# Adafruit_AirLift_Breakout.net
KiCad netlist of a schematic drawn in EAGLE
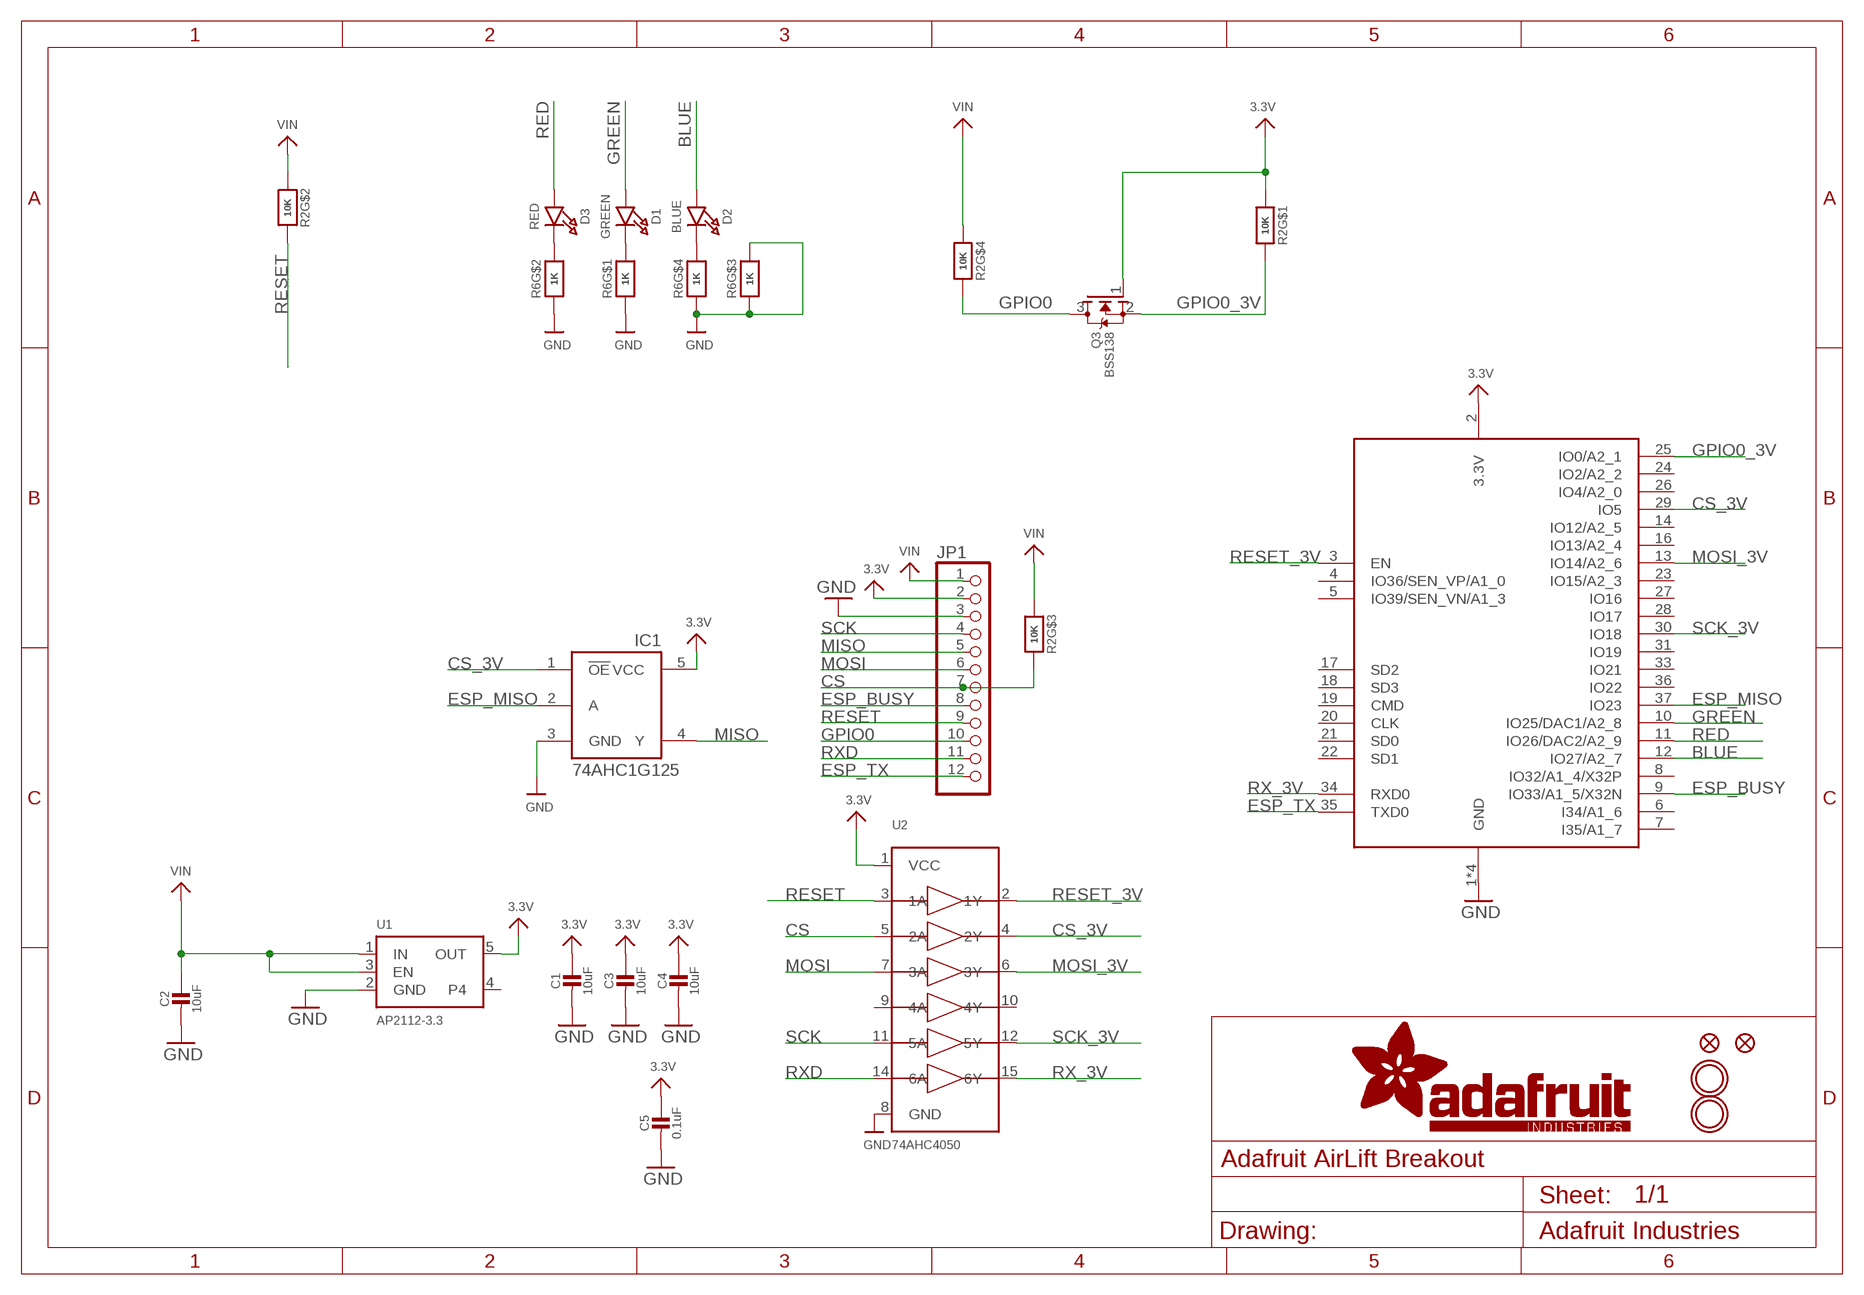
[diagram p0: schematic, sheet 1]

(export (version "E")
  (design (tool "Eeschema 10.0.6"))
  (components
    (comp (ref "C1")
      (value "10uF")
      (footprint "eagle-import:0805-NO")
      (libsource (lib "eagle-import") (part "CAP_CERAMIC0805-NOOUTLINE"))
    )
    (comp (ref "C2")
      (value "10uF")
      (footprint "eagle-import:0805-NO")
      (libsource (lib "eagle-import") (part "CAP_CERAMIC0805-NOOUTLINE"))
    )
    (comp (ref "C3")
      (value "10uF")
      (footprint "eagle-import:0805-NO")
      (libsource (lib "eagle-import") (part "CAP_CERAMIC0805-NOOUTLINE"))
    )
    (comp (ref "C4")
      (value "10uF")
      (footprint "eagle-import:0805-NO")
      (libsource (lib "eagle-import") (part "CAP_CERAMIC0805-NOOUTLINE"))
    )
    (comp (ref "C5")
      (value "0.1uF")
      (footprint "eagle-import:0603-NO")
      (libsource (lib "eagle-import") (part "CAP_CERAMIC0603_NO"))
    )
    (comp (ref "D1")
      (value "GREEN")
      (footprint "eagle-import:CHIPLED_0603_NOOUTLINE")
      (libsource (lib "eagle-import") (part "LED0603_NOOUTLINE"))
    )
    (comp (ref "D2")
      (value "BLUE")
      (footprint "eagle-import:CHIPLED_0603_NOOUTLINE")
      (libsource (lib "eagle-import") (part "LED0603_NOOUTLINE"))
    )
    (comp (ref "D3")
      (value "RED")
      (footprint "eagle-import:CHIPLED_0603_NOOUTLINE")
      (libsource (lib "eagle-import") (part "LED0603_NOOUTLINE"))
    )
    (comp (ref "FID1")
      (value "FIDUCIAL_1MM")
      (footprint "eagle-import:FIDUCIAL_1MM")
      (libsource (lib "eagle-import") (part "FIDUCIAL_1MM"))
    )
    (comp (ref "FID3")
      (value "FIDUCIAL_1MM")
      (footprint "eagle-import:FIDUCIAL_1MM")
      (libsource (lib "eagle-import") (part "FIDUCIAL_1MM"))
    )
    (comp (ref "IC1")
      (value "74AHC1G125")
      (footprint "eagle-import:SOT23-5L")
      (libsource (lib "eagle-import") (part "74AHC1G125"))
    )
    (comp (ref "JP1")
      (value "HEADER-1X12")
      (footprint "eagle-import:1X12_ROUND")
      (libsource (lib "eagle-import") (part "HEADER-1X12"))
    )
    (comp (ref "Q3")
      (value "BSS138")
      (footprint "eagle-import:SOT23-WIDE")
      (libsource (lib "eagle-import") (part "MOSFET-NWIDE"))
    )
    (comp (ref "R2")
      (value "10K")
      (footprint "eagle-import:RESPACK_4X0603")
      (libsource (lib "eagle-import") (part "RESISTOR_4PACK"))
    )
    (comp (ref "R6")
      (value "1K")
      (footprint "eagle-import:RESPACK_4X0603")
      (libsource (lib "eagle-import") (part "RESISTOR_4PACK"))
    )
    (comp (ref "U$15")
      (value "MOUNTINGHOLE2.5")
      (footprint "eagle-import:MOUNTINGHOLE_2.5_PLATED")
      (libsource (lib "eagle-import") (part "MOUNTINGHOLE2.5"))
    )
    (comp (ref "U$16")
      (value "MOUNTINGHOLE2.5")
      (footprint "eagle-import:MOUNTINGHOLE_2.5_PLATED")
      (libsource (lib "eagle-import") (part "MOUNTINGHOLE2.5"))
    )
    (comp (ref "U1")
      (value "AP2112-3.3")
      (footprint "eagle-import:SOT23-5")
      (libsource (lib "eagle-import") (part "VREG_SOT23-5"))
    )
    (comp (ref "U2")
      (value "74AHC4050")
      (footprint "eagle-import:TSSOP16")
      (libsource (lib "eagle-import") (part "74HC4050DTSSOP"))
    )
    (comp (ref "X1")
      (value "ESP32_WROOM32")
      (footprint "eagle-import:WROOM32")
      (libsource (lib "eagle-import") (part "ESP32_WROOM32"))
    )
  )
  (nets
    (net (code "1") (name "/BLUE") (class "Default")
      (node (ref "D2") (pin "A") (pinfunction "A_A") (pintype "passive"))
      (node (ref "X1") (pin "12") (pinfunction "IO27/A2_7_12") (pintype "bidirectional"))
    )
    (net (code "2") (name "/CS") (class "Default")
      (node (ref "JP1") (pin "7") (pinfunction "7_7") (pintype "passive"))
      (node (ref "R2") (pin "6") (pinfunction "2_6") (pintype "passive"))
      (node (ref "U2") (pin "5") (pinfunction "2A_5") (pintype "bidirectional"))
    )
    (net (code "3") (name "/CS_3V") (class "Default")
      (node (ref "IC1") (pin "1") (pinfunction "~{OE}_1") (pintype "input"))
      (node (ref "U2") (pin "4") (pinfunction "2Y_4") (pintype "bidirectional"))
      (node (ref "X1") (pin "29") (pinfunction "IO5_29") (pintype "bidirectional"))
    )
    (net (code "4") (name "/ESP_BUSY") (class "Default")
      (node (ref "JP1") (pin "8") (pinfunction "8_8") (pintype "passive"))
      (node (ref "X1") (pin "9") (pinfunction "IO33/A1_5/X32N_9") (pintype "bidirectional"))
    )
    (net (code "5") (name "/ESP_MISO") (class "Default")
      (node (ref "IC1") (pin "2") (pinfunction "A_2") (pintype "input"))
      (node (ref "X1") (pin "37") (pinfunction "IO23_37") (pintype "bidirectional"))
    )
    (net (code "6") (name "/ESP_TX") (class "Default")
      (node (ref "JP1") (pin "12") (pinfunction "12_12") (pintype "passive"))
      (node (ref "X1") (pin "35") (pinfunction "TXD0_35") (pintype "output"))
    )
    (net (code "7") (name "/GPIO0") (class "Default")
      (node (ref "JP1") (pin "10") (pinfunction "10_10") (pintype "passive"))
      (node (ref "Q3") (pin "3") (pinfunction "D_3") (pintype "bidirectional"))
      (node (ref "R2") (pin "4") (pinfunction "1_4") (pintype "passive"))
    )
    (net (code "8") (name "/GPIO0_3V") (class "Default")
      (node (ref "Q3") (pin "2") (pinfunction "S_2") (pintype "bidirectional"))
      (node (ref "R2") (pin "1") (pinfunction "1_1") (pintype "passive"))
      (node (ref "X1") (pin "25") (pinfunction "IO0/A2_1_25") (pintype "bidirectional"))
    )
    (net (code "9") (name "/GREEN") (class "Default")
      (node (ref "D1") (pin "A") (pinfunction "A_A") (pintype "passive"))
      (node (ref "X1") (pin "10") (pinfunction "IO25/DAC1/A2_8_10") (pintype "bidirectional"))
    )
    (net (code "10") (name "/MISO") (class "Default")
      (node (ref "IC1") (pin "4") (pinfunction "Y_4") (pintype "output"))
      (node (ref "JP1") (pin "5") (pinfunction "5_5") (pintype "passive"))
    )
    (net (code "11") (name "/MOSI") (class "Default")
      (node (ref "JP1") (pin "6") (pinfunction "6_6") (pintype "passive"))
      (node (ref "U2") (pin "7") (pinfunction "3A_7") (pintype "bidirectional"))
    )
    (net (code "12") (name "/MOSI_3V") (class "Default")
      (node (ref "U2") (pin "6") (pinfunction "3Y_6") (pintype "bidirectional"))
      (node (ref "X1") (pin "13") (pinfunction "IO14/A2_6_13") (pintype "bidirectional"))
    )
    (net (code "13") (name "/RED") (class "Default")
      (node (ref "D3") (pin "A") (pinfunction "A_A") (pintype "passive"))
      (node (ref "X1") (pin "11") (pinfunction "IO26/DAC2/A2_9_11") (pintype "bidirectional"))
    )
    (net (code "14") (name "/RESET") (class "Default")
      (node (ref "JP1") (pin "9") (pinfunction "9_9") (pintype "passive"))
      (node (ref "R2") (pin "7") (pinfunction "2_7") (pintype "passive"))
      (node (ref "U2") (pin "3") (pinfunction "1A_3") (pintype "bidirectional"))
    )
    (net (code "15") (name "/RESET_3V") (class "Default")
      (node (ref "U2") (pin "2") (pinfunction "1Y_2") (pintype "bidirectional"))
      (node (ref "X1") (pin "3") (pinfunction "EN_3") (pintype "input"))
    )
    (net (code "16") (name "/RXD") (class "Default")
      (node (ref "JP1") (pin "11") (pinfunction "11_11") (pintype "passive"))
      (node (ref "U2") (pin "14") (pinfunction "6A_14") (pintype "bidirectional"))
    )
    (net (code "17") (name "/RX_3V") (class "Default")
      (node (ref "U2") (pin "15") (pinfunction "6Y_15") (pintype "bidirectional"))
      (node (ref "X1") (pin "34") (pinfunction "RXD0_34") (pintype "input"))
    )
    (net (code "18") (name "/SCK") (class "Default")
      (node (ref "JP1") (pin "4") (pinfunction "4_4") (pintype "passive"))
      (node (ref "U2") (pin "11") (pinfunction "5A_11") (pintype "bidirectional"))
    )
    (net (code "19") (name "/SCK_3V") (class "Default")
      (node (ref "U2") (pin "12") (pinfunction "5Y_12") (pintype "bidirectional"))
      (node (ref "X1") (pin "30") (pinfunction "IO18_30") (pintype "bidirectional"))
    )
    (net (code "20") (name "3.3V") (class "Default")
      (node (ref "C1") (pin "1") (pinfunction "1_1") (pintype "passive"))
      (node (ref "C3") (pin "1") (pinfunction "1_1") (pintype "passive"))
      (node (ref "C4") (pin "1") (pinfunction "1_1") (pintype "passive"))
      (node (ref "C5") (pin "1") (pinfunction "1_1") (pintype "passive"))
      (node (ref "IC1") (pin "5") (pinfunction "VCC_5") (pintype "power_in"))
      (node (ref "JP1") (pin "2") (pinfunction "2_2") (pintype "passive"))
      (node (ref "Q3") (pin "1") (pinfunction "G_1") (pintype "bidirectional"))
      (node (ref "R2") (pin "8") (pinfunction "2_8") (pintype "passive"))
      (node (ref "U1") (pin "5") (pinfunction "OUT_5") (pintype "power_in"))
      (node (ref "U2") (pin "1") (pinfunction "VCC_1") (pintype "bidirectional"))
      (node (ref "X1") (pin "2") (pinfunction "3.3V_2") (pintype "passive"))
    )
    (net (code "21") (name "GND") (class "Default")
      (node (ref "C1") (pin "2") (pinfunction "2_2") (pintype "passive"))
      (node (ref "C2") (pin "2") (pinfunction "2_2") (pintype "passive"))
      (node (ref "C3") (pin "2") (pinfunction "2_2") (pintype "passive"))
      (node (ref "C4") (pin "2") (pinfunction "2_2") (pintype "passive"))
      (node (ref "C5") (pin "2") (pinfunction "2_2") (pintype "passive"))
      (node (ref "IC1") (pin "3") (pinfunction "GND_3") (pintype "power_in"))
      (node (ref "JP1") (pin "3") (pinfunction "3_3") (pintype "passive"))
      (node (ref "R6") (pin "1") (pinfunction "1_1") (pintype "passive"))
      (node (ref "R6") (pin "2") (pinfunction "1_2") (pintype "passive"))
      (node (ref "R6") (pin "3") (pinfunction "1_3") (pintype "passive"))
      (node (ref "R6") (pin "4") (pinfunction "1_4") (pintype "passive"))
      (node (ref "R6") (pin "6") (pinfunction "2_6") (pintype "passive"))
      (node (ref "U1") (pin "2") (pinfunction "GND_2") (pintype "power_in"))
      (node (ref "U2") (pin "8") (pinfunction "GND_8") (pintype "bidirectional"))
      (node (ref "X1") (pin "1") (pinfunction "GND_1") (pintype "passive"))
      (node (ref "X1") (pin "15") (pinfunction "GND_15") (pintype "passive"))
      (node (ref "X1") (pin "38") (pinfunction "GND_38") (pintype "passive"))
      (node (ref "X1") (pin "P$1") (pinfunction "GND_P$1") (pintype "passive"))
    )
    (net (code "22") (name "Net-(R6A-2)") (class "Default")
      (node (ref "D1") (pin "C") (pinfunction "C_C") (pintype "passive"))
      (node (ref "R6") (pin "8") (pinfunction "2_8") (pintype "passive"))
    )
    (net (code "23") (name "Net-(R6B-2)") (class "Default")
      (node (ref "D3") (pin "C") (pinfunction "C_C") (pintype "passive"))
      (node (ref "R6") (pin "7") (pinfunction "2_7") (pintype "passive"))
    )
    (net (code "24") (name "Net-(R6D-2)") (class "Default")
      (node (ref "D2") (pin "C") (pinfunction "C_C") (pintype "passive"))
      (node (ref "R6") (pin "5") (pinfunction "2_5") (pintype "passive"))
    )
    (net (code "25") (name "VIN") (class "Default")
      (node (ref "C2") (pin "1") (pinfunction "1_1") (pintype "passive"))
      (node (ref "JP1") (pin "1") (pinfunction "1_1") (pintype "passive"))
      (node (ref "R2") (pin "2") (pinfunction "1_2") (pintype "passive"))
      (node (ref "R2") (pin "3") (pinfunction "1_3") (pintype "passive"))
      (node (ref "R2") (pin "5") (pinfunction "2_5") (pintype "passive"))
      (node (ref "U1") (pin "1") (pinfunction "IN_1") (pintype "power_in"))
      (node (ref "U1") (pin "3") (pinfunction "EN_3") (pintype "input"))
    )
    (net (code "26") (name "unconnected-(U1-P4-Pad4)") (class "Default")
      (node (ref "U1") (pin "4") (pinfunction "P4_4") (pintype "bidirectional"))
    )
    (net (code "27") (name "unconnected-(U2-4A-Pad9)") (class "Default")
      (node (ref "U2") (pin "9") (pinfunction "4A_9") (pintype "bidirectional"))
    )
    (net (code "28") (name "unconnected-(U2-4Y-Pad10)") (class "Default")
      (node (ref "U2") (pin "10") (pinfunction "4Y_10") (pintype "bidirectional"))
    )
    (net (code "29") (name "unconnected-(X1-CLK-Pad20)") (class "Default")
      (node (ref "X1") (pin "20") (pinfunction "CLK_20") (pintype "bidirectional"))
    )
    (net (code "30") (name "unconnected-(X1-CMD-Pad19)") (class "Default")
      (node (ref "X1") (pin "19") (pinfunction "CMD_19") (pintype "bidirectional"))
    )
    (net (code "31") (name "unconnected-(X1-I34{slash}A1_6-Pad6)") (class "Default")
      (node (ref "X1") (pin "6") (pinfunction "I34/A1_6_6") (pintype "bidirectional"))
    )
    (net (code "32") (name "unconnected-(X1-I35{slash}A1_7-Pad7)") (class "Default")
      (node (ref "X1") (pin "7") (pinfunction "I35/A1_7_7") (pintype "bidirectional"))
    )
    (net (code "33") (name "unconnected-(X1-IO2{slash}A2_2-Pad24)") (class "Default")
      (node (ref "X1") (pin "24") (pinfunction "IO2/A2_2_24") (pintype "bidirectional"))
    )
    (net (code "34") (name "unconnected-(X1-IO4{slash}A2_0-Pad26)") (class "Default")
      (node (ref "X1") (pin "26") (pinfunction "IO4/A2_0_26") (pintype "bidirectional"))
    )
    (net (code "35") (name "unconnected-(X1-IO12{slash}A2_5-Pad14)") (class "Default")
      (node (ref "X1") (pin "14") (pinfunction "IO12/A2_5_14") (pintype "bidirectional"))
    )
    (net (code "36") (name "unconnected-(X1-IO13{slash}A2_4-Pad16)") (class "Default")
      (node (ref "X1") (pin "16") (pinfunction "IO13/A2_4_16") (pintype "bidirectional"))
    )
    (net (code "37") (name "unconnected-(X1-IO15{slash}A2_3-Pad23)") (class "Default")
      (node (ref "X1") (pin "23") (pinfunction "IO15/A2_3_23") (pintype "bidirectional"))
    )
    (net (code "38") (name "unconnected-(X1-IO16-Pad27)") (class "Default")
      (node (ref "X1") (pin "27") (pinfunction "IO16_27") (pintype "bidirectional"))
    )
    (net (code "39") (name "unconnected-(X1-IO17-Pad28)") (class "Default")
      (node (ref "X1") (pin "28") (pinfunction "IO17_28") (pintype "bidirectional"))
    )
    (net (code "40") (name "unconnected-(X1-IO19-Pad31)") (class "Default")
      (node (ref "X1") (pin "31") (pinfunction "IO19_31") (pintype "bidirectional"))
    )
    (net (code "41") (name "unconnected-(X1-IO21-Pad33)") (class "Default")
      (node (ref "X1") (pin "33") (pinfunction "IO21_33") (pintype "bidirectional"))
    )
    (net (code "42") (name "unconnected-(X1-IO22-Pad36)") (class "Default")
      (node (ref "X1") (pin "36") (pinfunction "IO22_36") (pintype "bidirectional"))
    )
    (net (code "43") (name "unconnected-(X1-IO32{slash}A1_4{slash}X32P-Pad8)") (class "Default")
      (node (ref "X1") (pin "8") (pinfunction "IO32/A1_4/X32P_8") (pintype "bidirectional"))
    )
    (net (code "44") (name "unconnected-(X1-IO36{slash}SEN_VP{slash}A1_0-Pad4)") (class "Default")
      (node (ref "X1") (pin "4") (pinfunction "IO36/SEN_VP/A1_0_4") (pintype "passive"))
    )
    (net (code "45") (name "unconnected-(X1-IO39{slash}SEN_VN{slash}A1_3-Pad5)") (class "Default")
      (node (ref "X1") (pin "5") (pinfunction "IO39/SEN_VN/A1_3_5") (pintype "passive"))
    )
    (net (code "46") (name "unconnected-(X1-SD0-Pad21)") (class "Default")
      (node (ref "X1") (pin "21") (pinfunction "SD0_21") (pintype "bidirectional"))
    )
    (net (code "47") (name "unconnected-(X1-SD1-Pad22)") (class "Default")
      (node (ref "X1") (pin "22") (pinfunction "SD1_22") (pintype "bidirectional"))
    )
    (net (code "48") (name "unconnected-(X1-SD2-Pad17)") (class "Default")
      (node (ref "X1") (pin "17") (pinfunction "SD2_17") (pintype "bidirectional"))
    )
    (net (code "49") (name "unconnected-(X1-SD3-Pad18)") (class "Default")
      (node (ref "X1") (pin "18") (pinfunction "SD3_18") (pintype "bidirectional"))
    )
  )
)
